# Mcu.net
KiCad netlist of a schematic drawn in Altium Designer
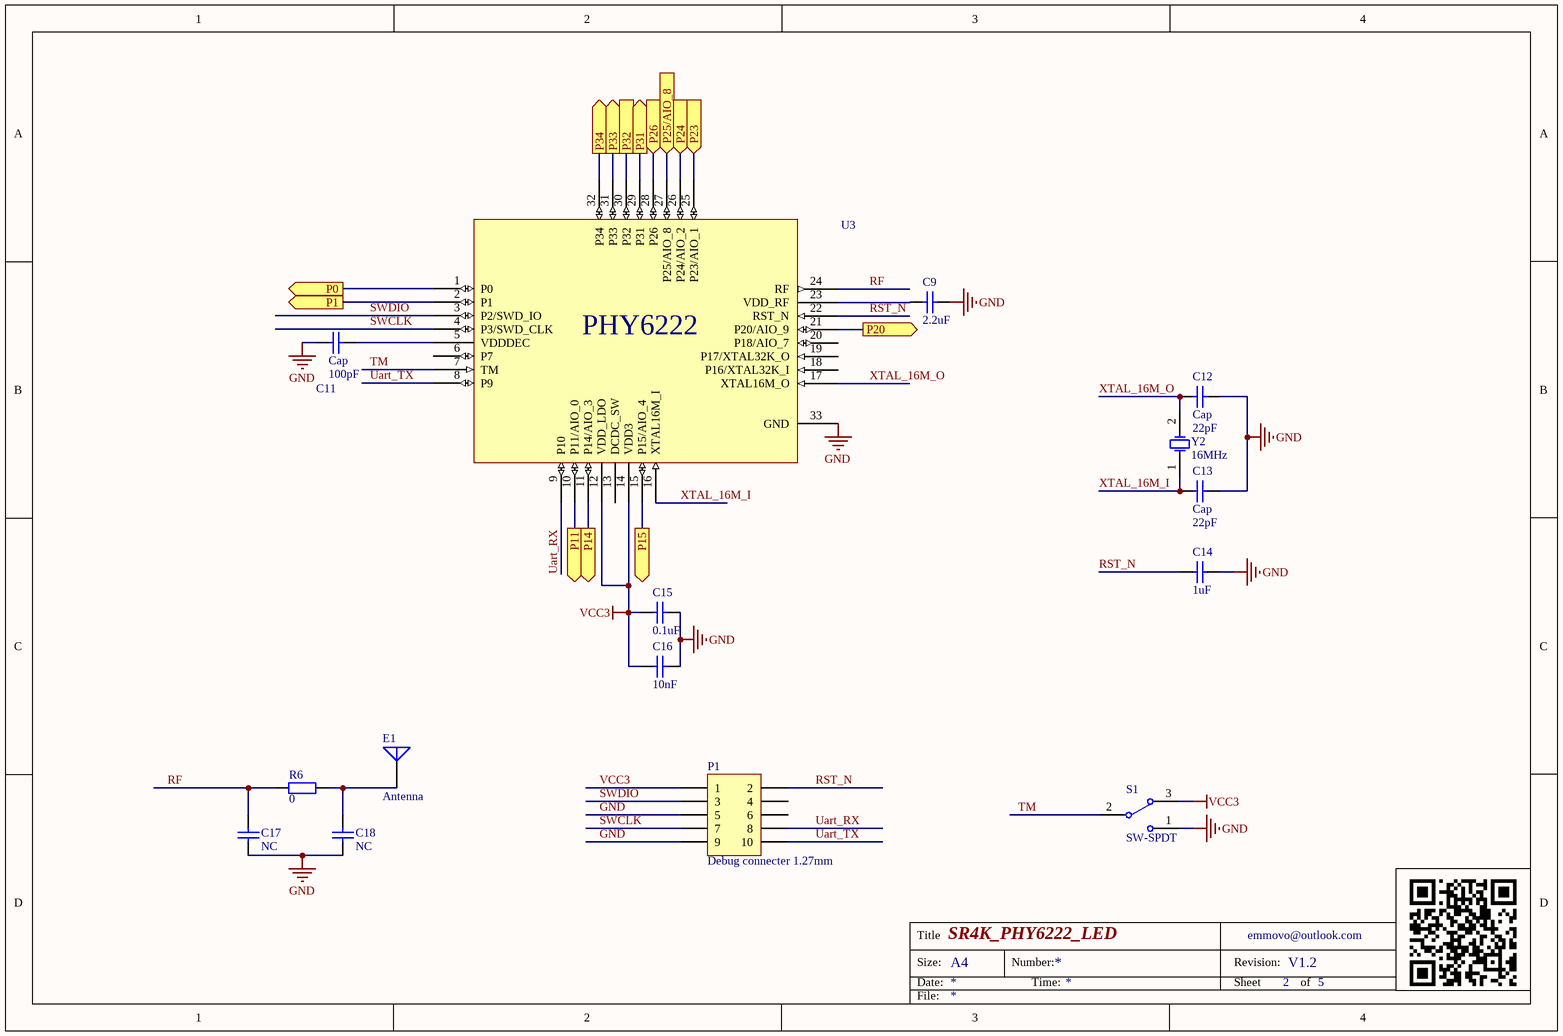
[diagram p0: Mcu.SchDoc]

(export (version "E")
  (design (tool "Eeschema 10.0.6"))
  (components
    (comp (ref "C9")
      (value "2.2uF")
      (description "Capacitor")
      (fields (field (name "Comment") "Cap") (field (name "PUBLISHER") "Altium Limited"))
      (libsource (lib "Miscellaneous Devices") (part "Cap"))
    )
    (comp (ref "C11")
      (value "Cap")
      (description "Capacitor")
      (fields (field (name "ALTIUM_VALUE") "100pF") (field (name "PUBLISHER") "Altium Limited"))
      (libsource (lib "Miscellaneous Devices") (part "Cap"))
    )
    (comp (ref "C12")
      (value "Cap")
      (description "Capacitor")
      (fields (field (name "ALTIUM_VALUE") "22pF") (field (name "PUBLISHER") "Altium Limited"))
      (libsource (lib "Miscellaneous Devices") (part "Cap"))
    )
    (comp (ref "C13")
      (value "Cap")
      (description "Capacitor")
      (fields (field (name "ALTIUM_VALUE") "22pF") (field (name "PUBLISHER") "Altium Limited"))
      (libsource (lib "Miscellaneous Devices") (part "Cap"))
    )
    (comp (ref "C14")
      (value "1uF")
      (description "Capacitor")
      (fields (field (name "Comment") "Cap") (field (name "PUBLISHER") "Altium Limited"))
      (libsource (lib "Miscellaneous Devices") (part "Cap"))
    )
    (comp (ref "C15")
      (value "0.1uF")
      (description "Capacitor")
      (fields (field (name "Comment") "Cap") (field (name "PUBLISHER") "Altium Limited"))
      (libsource (lib "Miscellaneous Devices") (part "Cap"))
    )
    (comp (ref "C16")
      (value "10nF")
      (description "Capacitor")
      (fields (field (name "Comment") "Cap") (field (name "PUBLISHER") "Altium Limited"))
      (libsource (lib "Miscellaneous Devices") (part "Cap"))
    )
    (comp (ref "C17")
      (value "NC")
      (description "Capacitor")
      (fields (field (name "Comment") "Cap") (field (name "PUBLISHER") "Altium Limited"))
      (libsource (lib "Miscellaneous Devices") (part "Cap"))
    )
    (comp (ref "C18")
      (value "NC")
      (description "Capacitor")
      (fields (field (name "Comment") "Cap") (field (name "PUBLISHER") "Altium Limited"))
      (libsource (lib "Miscellaneous Devices") (part "Cap"))
    )
    (comp (ref "E1")
      (value "Antenna")
      (footprint "PIN1")
      (description "Generic Antenna")
      (fields (field (name "PUBLISHER") "Altium Limited"))
      (libsource (lib "Miscellaneous Devices") (part "Antenna"))
    )
    (comp (ref "P1")
      (value "Debug connecter 1.27mm")
      (description "Header, 5-Pin, Dual row")
      (fields (field (name "PUBLISHER") "Altium Limited"))
      (libsource (lib "Miscellaneous Connectors") (part "Header 5X2"))
    )
    (comp (ref "R6")
      (value "0")
      (description "Resistor")
      (fields (field (name "PUBLISHER") "Altium Limited"))
      (libsource (lib "Miscellaneous Devices") (part "Res2"))
    )
    (comp (ref "S1")
      (value "SW-SPDT")
      (description "SPDT Subminiature Toggle Switch, Right Angle Mounting, Vertical Actuation")
      (fields (field (name "PUBLISHER") "Altium Limited"))
      (libsource (lib "Miscellaneous Devices") (part "SW-SPDT"))
    )
    (comp (ref "U3") (value "U*") (libsource (lib "Schlib") (part "PHY6222")))
    (comp (ref "Y2")
      (value "16MHz")
      (description "Crystal Oscillator")
      (fields (field (name "PUBLISHER") "Altium Limited"))
      (libsource (lib "Miscellaneous Devices") (part "XTAL"))
    )
  )
  (nets
    (net (code "1") (name "/P0") (class "Default")
      (node (ref "U3") (pin "1") (pinfunction "P0_1") (pintype "bidirectional"))
    )
    (net (code "2") (name "/P1") (class "Default")
      (node (ref "U3") (pin "2") (pinfunction "P1_2") (pintype "bidirectional"))
    )
    (net (code "3") (name "/P11") (class "Default")
      (node (ref "U3") (pin "10") (pinfunction "P11/AIO_0_10") (pintype "bidirectional"))
    )
    (net (code "4") (name "/P14") (class "Default")
      (node (ref "U3") (pin "11") (pinfunction "P14/AIO_3_11") (pintype "bidirectional"))
    )
    (net (code "5") (name "/P15") (class "Default")
      (node (ref "U3") (pin "15") (pinfunction "P15/AIO_4_15") (pintype "bidirectional"))
    )
    (net (code "6") (name "/P20") (class "Default")
      (node (ref "U3") (pin "21") (pinfunction "P20/AIO_9_21") (pintype "bidirectional"))
    )
    (net (code "7") (name "/P23") (class "Default")
      (node (ref "U3") (pin "25") (pinfunction "P23/AIO_1_25") (pintype "bidirectional"))
    )
    (net (code "8") (name "/P24") (class "Default")
      (node (ref "U3") (pin "26") (pinfunction "P24/AIO_2_26") (pintype "bidirectional"))
    )
    (net (code "9") (name "/P25{slash}AIO_8") (class "Default")
      (node (ref "U3") (pin "27") (pinfunction "P25/AIO_8_27") (pintype "bidirectional"))
    )
    (net (code "10") (name "/P26") (class "Default")
      (node (ref "U3") (pin "28") (pinfunction "P26_28") (pintype "bidirectional"))
    )
    (net (code "11") (name "/P31") (class "Default")
      (node (ref "U3") (pin "29") (pinfunction "P31_29") (pintype "bidirectional"))
    )
    (net (code "12") (name "/P32") (class "Default")
      (node (ref "U3") (pin "30") (pinfunction "P32_30") (pintype "bidirectional"))
    )
    (net (code "13") (name "/P33") (class "Default")
      (node (ref "U3") (pin "31") (pinfunction "P33_31") (pintype "bidirectional"))
    )
    (net (code "14") (name "/P34") (class "Default")
      (node (ref "U3") (pin "32") (pinfunction "P34_32") (pintype "bidirectional"))
    )
    (net (code "15") (name "/RF") (class "Default")
      (node (ref "C17") (pin "1") (pinfunction "1_1") (pintype "passive"))
      (node (ref "R6") (pin "2") (pinfunction "2_2") (pintype "passive"))
      (node (ref "U3") (pin "24") (pinfunction "RF_24") (pintype "output"))
    )
    (net (code "16") (name "/RST_N") (class "Default")
      (node (ref "C14") (pin "1") (pinfunction "1_1") (pintype "passive"))
      (node (ref "P1") (pin "2") (pinfunction "2_2") (pintype "passive"))
      (node (ref "U3") (pin "22") (pinfunction "RST_N_22") (pintype "input"))
    )
    (net (code "17") (name "/SWCLK") (class "Default")
      (node (ref "P1") (pin "7") (pinfunction "7_7") (pintype "passive"))
      (node (ref "U3") (pin "4") (pinfunction "P3/SWD_CLK_4") (pintype "bidirectional"))
    )
    (net (code "18") (name "/SWDIO") (class "Default")
      (node (ref "P1") (pin "3") (pinfunction "3_3") (pintype "passive"))
      (node (ref "U3") (pin "3") (pinfunction "P2/SWD_IO_3") (pintype "bidirectional"))
    )
    (net (code "19") (name "/TM") (class "Default")
      (node (ref "S1") (pin "2") (pinfunction "2_2") (pintype "passive"))
      (node (ref "U3") (pin "7") (pinfunction "TM_7") (pintype "input"))
    )
    (net (code "20") (name "/Uart_RX") (class "Default")
      (node (ref "P1") (pin "8") (pinfunction "8_8") (pintype "passive"))
      (node (ref "U3") (pin "9") (pinfunction "P10_9") (pintype "bidirectional"))
    )
    (net (code "21") (name "/Uart_TX") (class "Default")
      (node (ref "P1") (pin "10") (pinfunction "10_10") (pintype "passive"))
      (node (ref "U3") (pin "8") (pinfunction "P9_8") (pintype "bidirectional"))
    )
    (net (code "22") (name "/XTAL_16M_I") (class "Default")
      (node (ref "C13") (pin "2") (pinfunction "2_2") (pintype "passive"))
      (node (ref "U3") (pin "16") (pinfunction "XTAL16M_I_16") (pintype "input"))
      (node (ref "Y2") (pin "1") (pinfunction "OSC1_1") (pintype "passive"))
    )
    (net (code "23") (name "/XTAL_16M_O") (class "Default")
      (node (ref "C12") (pin "2") (pinfunction "2_2") (pintype "passive"))
      (node (ref "U3") (pin "17") (pinfunction "XTAL16M_O_17") (pintype "input"))
      (node (ref "Y2") (pin "2") (pinfunction "OSC2_2") (pintype "passive"))
    )
    (net (code "24") (name "GND") (class "Default")
      (node (ref "C11") (pin "1") (pinfunction "1_1") (pintype "passive"))
      (node (ref "C12") (pin "1") (pinfunction "1_1") (pintype "passive"))
      (node (ref "C13") (pin "1") (pinfunction "1_1") (pintype "passive"))
      (node (ref "C14") (pin "2") (pinfunction "2_2") (pintype "passive"))
      (node (ref "C15") (pin "2") (pinfunction "2_2") (pintype "passive"))
      (node (ref "C16") (pin "2") (pinfunction "2_2") (pintype "passive"))
      (node (ref "C17") (pin "2") (pinfunction "2_2") (pintype "passive"))
      (node (ref "C18") (pin "2") (pinfunction "2_2") (pintype "passive"))
      (node (ref "C9") (pin "2") (pinfunction "2_2") (pintype "passive"))
      (node (ref "P1") (pin "5") (pinfunction "5_5") (pintype "passive"))
      (node (ref "P1") (pin "9") (pinfunction "9_9") (pintype "passive"))
      (node (ref "S1") (pin "1") (pinfunction "1_1") (pintype "passive"))
      (node (ref "U3") (pin "33") (pinfunction "GND_33") (pintype "power_in"))
    )
    (net (code "25") (name "Net-(E1-A)") (class "Default")
      (node (ref "C18") (pin "1") (pinfunction "1_1") (pintype "passive"))
      (node (ref "E1") (pin "1") (pinfunction "A_1") (pintype "passive"))
      (node (ref "R6") (pin "1") (pinfunction "1_1") (pintype "passive"))
    )
    (net (code "26") (name "Net-(U3-VDD3)") (class "Default")
      (node (ref "C15") (pin "1") (pinfunction "1_1") (pintype "passive"))
      (node (ref "C16") (pin "1") (pinfunction "1_1") (pintype "passive"))
      (node (ref "U3") (pin "12") (pinfunction "VDD_LDO_12") (pintype "power_in"))
      (node (ref "U3") (pin "14") (pinfunction "VDD3_14") (pintype "power_in"))
    )
    (net (code "27") (name "Net-(U3-VDDDEC)") (class "Default")
      (node (ref "C11") (pin "2") (pinfunction "2_2") (pintype "passive"))
      (node (ref "U3") (pin "5") (pinfunction "VDDDEC_5") (pintype "power_in"))
    )
    (net (code "28") (name "Net-(U3-VDD_RF)") (class "Default")
      (node (ref "C9") (pin "1") (pinfunction "1_1") (pintype "passive"))
      (node (ref "U3") (pin "23") (pinfunction "VDD_RF_23") (pintype "power_in"))
    )
    (net (code "29") (name "VCC3") (class "Default")
      (node (ref "P1") (pin "1") (pinfunction "1_1") (pintype "passive"))
      (node (ref "S1") (pin "3") (pinfunction "3_3") (pintype "passive"))
    )
    (net (code "30") (name "unconnected-(P1-Pad4)") (class "Default")
      (node (ref "P1") (pin "4") (pinfunction "4_4") (pintype "passive"))
    )
    (net (code "31") (name "unconnected-(P1-Pad6)") (class "Default")
      (node (ref "P1") (pin "6") (pinfunction "6_6") (pintype "passive"))
    )
    (net (code "32") (name "unconnected-(U3-DCDC_SW-Pad13)") (class "Default")
      (node (ref "U3") (pin "13") (pinfunction "DCDC_SW_13") (pintype "power_in"))
    )
    (net (code "33") (name "unconnected-(U3-P7-Pad6)") (class "Default")
      (node (ref "U3") (pin "6") (pinfunction "P7_6") (pintype "bidirectional"))
    )
    (net (code "34") (name "unconnected-(U3-P16{slash}XTAL32K_I-Pad18)") (class "Default")
      (node (ref "U3") (pin "18") (pinfunction "P16/XTAL32K_I_18") (pintype "input"))
    )
    (net (code "35") (name "unconnected-(U3-P17{slash}XTAL32K_O-Pad19)") (class "Default")
      (node (ref "U3") (pin "19") (pinfunction "P17/XTAL32K_O_19") (pintype "input"))
    )
    (net (code "36") (name "unconnected-(U3-P18{slash}AIO_7-Pad20)") (class "Default")
      (node (ref "U3") (pin "20") (pinfunction "P18/AIO_7_20") (pintype "bidirectional"))
    )
  )
)
